# reDotSmart_0402_rev2.net
KiCad netlist of a schematic drawn in EAGLE
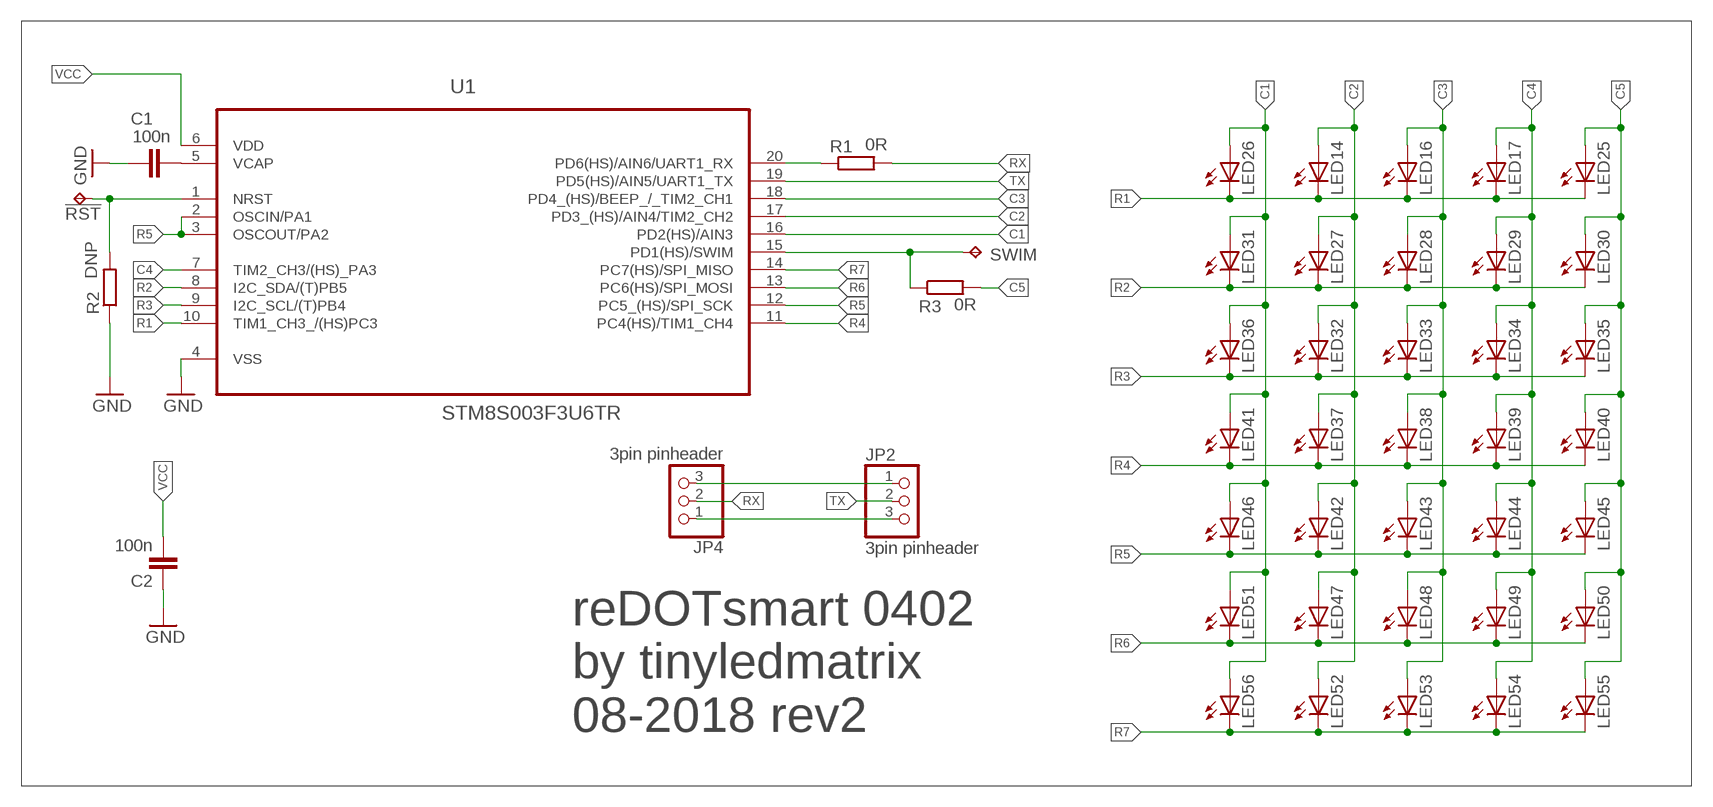
[diagram p0: schematic, sheet 1]

(export (version "E")
  (design (tool "Eeschema 10.0.6"))
  (components
    (comp (ref "!RST")
      (value "TPTP10R")
      (footprint "eagle-import:TP10R")
      (libsource (lib "eagle-import") (part "TPTP10R"))
    )
    (comp (ref "C1")
      (value "100n")
      (footprint "eagle-import:C0402-VISHAY")
      (libsource (lib "eagle-import") (part "C-EU0402_VISHAY"))
    )
    (comp (ref "C2")
      (value "100n")
      (footprint "eagle-import:C0402-VISHAY")
      (libsource (lib "eagle-import") (part "C-EU0402_VISHAY"))
    )
    (comp (ref "JP2")
      (value "3pin pinheader")
      (footprint "eagle-import:1X03_ROUND_NOSM")
      (libsource (lib "eagle-import") (part "PINHD-1X3NOSM"))
    )
    (comp (ref "JP4")
      (value "3pin pinheader")
      (footprint "eagle-import:1X03_ROUND_NOSM")
      (libsource (lib "eagle-import") (part "PINHD-1X3NOSM"))
    )
    (comp (ref "LED14")
      (value "LED0402_ROHM")
      (footprint "eagle-import:LED0402_E_ROHM_SML-P1")
      (libsource (lib "eagle-import") (part "LED0402_ROHM"))
    )
    (comp (ref "LED16")
      (value "LED0402_ROHM")
      (footprint "eagle-import:LED0402_E_ROHM_SML-P1")
      (libsource (lib "eagle-import") (part "LED0402_ROHM"))
    )
    (comp (ref "LED17")
      (value "LED0402_ROHM")
      (footprint "eagle-import:LED0402_E_ROHM_SML-P1")
      (libsource (lib "eagle-import") (part "LED0402_ROHM"))
    )
    (comp (ref "LED25")
      (value "LED0402_ROHM")
      (footprint "eagle-import:LED0402_E_ROHM_SML-P1")
      (libsource (lib "eagle-import") (part "LED0402_ROHM"))
    )
    (comp (ref "LED26")
      (value "LED0402_ROHM")
      (footprint "eagle-import:LED0402_E_ROHM_SML-P1")
      (libsource (lib "eagle-import") (part "LED0402_ROHM"))
    )
    (comp (ref "LED27")
      (value "LED0402_ROHM")
      (footprint "eagle-import:LED0402_E_ROHM_SML-P1")
      (libsource (lib "eagle-import") (part "LED0402_ROHM"))
    )
    (comp (ref "LED28")
      (value "LED0402_ROHM")
      (footprint "eagle-import:LED0402_E_ROHM_SML-P1")
      (libsource (lib "eagle-import") (part "LED0402_ROHM"))
    )
    (comp (ref "LED29")
      (value "LED0402_ROHM")
      (footprint "eagle-import:LED0402_E_ROHM_SML-P1")
      (libsource (lib "eagle-import") (part "LED0402_ROHM"))
    )
    (comp (ref "LED30")
      (value "LED0402_ROHM")
      (footprint "eagle-import:LED0402_E_ROHM_SML-P1")
      (libsource (lib "eagle-import") (part "LED0402_ROHM"))
    )
    (comp (ref "LED31")
      (value "LED0402_ROHM")
      (footprint "eagle-import:LED0402_E_ROHM_SML-P1")
      (libsource (lib "eagle-import") (part "LED0402_ROHM"))
    )
    (comp (ref "LED32")
      (value "LED0402_ROHM")
      (footprint "eagle-import:LED0402_E_ROHM_SML-P1")
      (libsource (lib "eagle-import") (part "LED0402_ROHM"))
    )
    (comp (ref "LED33")
      (value "LED0402_ROHM")
      (footprint "eagle-import:LED0402_E_ROHM_SML-P1")
      (libsource (lib "eagle-import") (part "LED0402_ROHM"))
    )
    (comp (ref "LED34")
      (value "LED0402_ROHM")
      (footprint "eagle-import:LED0402_E_ROHM_SML-P1")
      (libsource (lib "eagle-import") (part "LED0402_ROHM"))
    )
    (comp (ref "LED35")
      (value "LED0402_ROHM")
      (footprint "eagle-import:LED0402_E_ROHM_SML-P1")
      (libsource (lib "eagle-import") (part "LED0402_ROHM"))
    )
    (comp (ref "LED36")
      (value "LED0402_ROHM")
      (footprint "eagle-import:LED0402_E_ROHM_SML-P1")
      (libsource (lib "eagle-import") (part "LED0402_ROHM"))
    )
    (comp (ref "LED37")
      (value "LED0402_ROHM")
      (footprint "eagle-import:LED0402_E_ROHM_SML-P1")
      (libsource (lib "eagle-import") (part "LED0402_ROHM"))
    )
    (comp (ref "LED38")
      (value "LED0402_ROHM")
      (footprint "eagle-import:LED0402_E_ROHM_SML-P1")
      (libsource (lib "eagle-import") (part "LED0402_ROHM"))
    )
    (comp (ref "LED39")
      (value "LED0402_ROHM")
      (footprint "eagle-import:LED0402_E_ROHM_SML-P1")
      (libsource (lib "eagle-import") (part "LED0402_ROHM"))
    )
    (comp (ref "LED40")
      (value "LED0402_ROHM")
      (footprint "eagle-import:LED0402_E_ROHM_SML-P1")
      (libsource (lib "eagle-import") (part "LED0402_ROHM"))
    )
    (comp (ref "LED41")
      (value "LED0402_ROHM")
      (footprint "eagle-import:LED0402_E_ROHM_SML-P1")
      (libsource (lib "eagle-import") (part "LED0402_ROHM"))
    )
    (comp (ref "LED42")
      (value "LED0402_ROHM")
      (footprint "eagle-import:LED0402_E_ROHM_SML-P1")
      (libsource (lib "eagle-import") (part "LED0402_ROHM"))
    )
    (comp (ref "LED43")
      (value "LED0402_ROHM")
      (footprint "eagle-import:LED0402_E_ROHM_SML-P1")
      (libsource (lib "eagle-import") (part "LED0402_ROHM"))
    )
    (comp (ref "LED44")
      (value "LED0402_ROHM")
      (footprint "eagle-import:LED0402_E_ROHM_SML-P1")
      (libsource (lib "eagle-import") (part "LED0402_ROHM"))
    )
    (comp (ref "LED45")
      (value "LED0402_ROHM")
      (footprint "eagle-import:LED0402_E_ROHM_SML-P1")
      (libsource (lib "eagle-import") (part "LED0402_ROHM"))
    )
    (comp (ref "LED46")
      (value "LED0402_ROHM")
      (footprint "eagle-import:LED0402_E_ROHM_SML-P1")
      (libsource (lib "eagle-import") (part "LED0402_ROHM"))
    )
    (comp (ref "LED47")
      (value "LED0402_ROHM")
      (footprint "eagle-import:LED0402_E_ROHM_SML-P1")
      (libsource (lib "eagle-import") (part "LED0402_ROHM"))
    )
    (comp (ref "LED48")
      (value "LED0402_ROHM")
      (footprint "eagle-import:LED0402_E_ROHM_SML-P1")
      (libsource (lib "eagle-import") (part "LED0402_ROHM"))
    )
    (comp (ref "LED49")
      (value "LED0402_ROHM")
      (footprint "eagle-import:LED0402_E_ROHM_SML-P1")
      (libsource (lib "eagle-import") (part "LED0402_ROHM"))
    )
    (comp (ref "LED50")
      (value "LED0402_ROHM")
      (footprint "eagle-import:LED0402_E_ROHM_SML-P1")
      (libsource (lib "eagle-import") (part "LED0402_ROHM"))
    )
    (comp (ref "LED51")
      (value "LED0402_ROHM")
      (footprint "eagle-import:LED0402_E_ROHM_SML-P1")
      (libsource (lib "eagle-import") (part "LED0402_ROHM"))
    )
    (comp (ref "LED52")
      (value "LED0402_ROHM")
      (footprint "eagle-import:LED0402_E_ROHM_SML-P1")
      (libsource (lib "eagle-import") (part "LED0402_ROHM"))
    )
    (comp (ref "LED53")
      (value "LED0402_ROHM")
      (footprint "eagle-import:LED0402_E_ROHM_SML-P1")
      (libsource (lib "eagle-import") (part "LED0402_ROHM"))
    )
    (comp (ref "LED54")
      (value "LED0402_ROHM")
      (footprint "eagle-import:LED0402_E_ROHM_SML-P1")
      (libsource (lib "eagle-import") (part "LED0402_ROHM"))
    )
    (comp (ref "LED55")
      (value "LED0402_ROHM")
      (footprint "eagle-import:LED0402_E_ROHM_SML-P1")
      (libsource (lib "eagle-import") (part "LED0402_ROHM"))
    )
    (comp (ref "LED56")
      (value "LED0402_ROHM")
      (footprint "eagle-import:LED0402_E_ROHM_SML-P1")
      (libsource (lib "eagle-import") (part "LED0402_ROHM"))
    )
    (comp (ref "R1")
      (value "0R")
      (footprint "eagle-import:ADAFRUIT_R0402-VISHAY")
      (libsource (lib "eagle-import") (part "R-EU_R0402-VISHAY"))
    )
    (comp (ref "R2")
      (value "DNP")
      (footprint "eagle-import:ADAFRUIT_R0402-VISHAY")
      (libsource (lib "eagle-import") (part "R-EU_R0402-VISHAY"))
    )
    (comp (ref "R3")
      (value "0R")
      (footprint "eagle-import:ADAFRUIT_R0603-VISHAY")
      (libsource (lib "eagle-import") (part "R-EU_R0603-VISHAY"))
    )
    (comp (ref "SWIM")
      (value "TPTP10R")
      (footprint "eagle-import:TP10R")
      (libsource (lib "eagle-import") (part "TPTP10R"))
    )
    (comp (ref "U1")
      (value "STM8S003F3U6TR")
      (footprint "eagle-import:QFN50P300X300X100-20N_STM")
      (libsource (lib "eagle-import") (part "STM8S003F3U6TR"))
    )
  )
  (nets
    (net (code "1") (name "C1") (class "Default")
      (node (ref "LED26") (pin "A") (pinfunction "A_A") (pintype "passive"))
      (node (ref "LED31") (pin "A") (pinfunction "A_A") (pintype "passive"))
      (node (ref "LED36") (pin "A") (pinfunction "A_A") (pintype "passive"))
      (node (ref "LED41") (pin "A") (pinfunction "A_A") (pintype "passive"))
      (node (ref "LED46") (pin "A") (pinfunction "A_A") (pintype "passive"))
      (node (ref "LED51") (pin "A") (pinfunction "A_A") (pintype "passive"))
      (node (ref "LED56") (pin "A") (pinfunction "A_A") (pintype "passive"))
      (node (ref "U1") (pin "16") (pinfunction "PD2(HS)/AIN3_16") (pintype "bidirectional"))
    )
    (net (code "2") (name "C2") (class "Default")
      (node (ref "LED14") (pin "A") (pinfunction "A_A") (pintype "passive"))
      (node (ref "LED27") (pin "A") (pinfunction "A_A") (pintype "passive"))
      (node (ref "LED32") (pin "A") (pinfunction "A_A") (pintype "passive"))
      (node (ref "LED37") (pin "A") (pinfunction "A_A") (pintype "passive"))
      (node (ref "LED42") (pin "A") (pinfunction "A_A") (pintype "passive"))
      (node (ref "LED47") (pin "A") (pinfunction "A_A") (pintype "passive"))
      (node (ref "LED52") (pin "A") (pinfunction "A_A") (pintype "passive"))
      (node (ref "U1") (pin "17") (pinfunction "PD3_(HS)/AIN4/TIM2_CH2_17") (pintype "bidirectional"))
    )
    (net (code "3") (name "C3") (class "Default")
      (node (ref "LED16") (pin "A") (pinfunction "A_A") (pintype "passive"))
      (node (ref "LED28") (pin "A") (pinfunction "A_A") (pintype "passive"))
      (node (ref "LED33") (pin "A") (pinfunction "A_A") (pintype "passive"))
      (node (ref "LED38") (pin "A") (pinfunction "A_A") (pintype "passive"))
      (node (ref "LED43") (pin "A") (pinfunction "A_A") (pintype "passive"))
      (node (ref "LED48") (pin "A") (pinfunction "A_A") (pintype "passive"))
      (node (ref "LED53") (pin "A") (pinfunction "A_A") (pintype "passive"))
      (node (ref "U1") (pin "18") (pinfunction "PD4_(HS)/BEEP_/_TIM2_CH1_18") (pintype "bidirectional"))
    )
    (net (code "4") (name "C4") (class "Default")
      (node (ref "LED17") (pin "A") (pinfunction "A_A") (pintype "passive"))
      (node (ref "LED29") (pin "A") (pinfunction "A_A") (pintype "passive"))
      (node (ref "LED34") (pin "A") (pinfunction "A_A") (pintype "passive"))
      (node (ref "LED39") (pin "A") (pinfunction "A_A") (pintype "passive"))
      (node (ref "LED44") (pin "A") (pinfunction "A_A") (pintype "passive"))
      (node (ref "LED49") (pin "A") (pinfunction "A_A") (pintype "passive"))
      (node (ref "LED54") (pin "A") (pinfunction "A_A") (pintype "passive"))
      (node (ref "U1") (pin "7") (pinfunction "TIM2_CH3/(HS)_PA3_7") (pintype "bidirectional"))
    )
    (net (code "5") (name "C5") (class "Default")
      (node (ref "LED25") (pin "A") (pinfunction "A_A") (pintype "passive"))
      (node (ref "LED30") (pin "A") (pinfunction "A_A") (pintype "passive"))
      (node (ref "LED35") (pin "A") (pinfunction "A_A") (pintype "passive"))
      (node (ref "LED40") (pin "A") (pinfunction "A_A") (pintype "passive"))
      (node (ref "LED45") (pin "A") (pinfunction "A_A") (pintype "passive"))
      (node (ref "LED50") (pin "A") (pinfunction "A_A") (pintype "passive"))
      (node (ref "LED55") (pin "A") (pinfunction "A_A") (pintype "passive"))
      (node (ref "R3") (pin "2") (pinfunction "2_2") (pintype "passive"))
    )
    (net (code "6") (name "GND") (class "Default")
      (node (ref "C1") (pin "1") (pinfunction "1_1") (pintype "passive"))
      (node (ref "C2") (pin "1") (pinfunction "1_1") (pintype "passive"))
      (node (ref "JP2") (pin "1") (pinfunction "1_1") (pintype "passive"))
      (node (ref "JP4") (pin "3") (pinfunction "3_3") (pintype "passive"))
      (node (ref "R2") (pin "1") (pinfunction "1_1") (pintype "passive"))
      (node (ref "U1") (pin "4") (pinfunction "VSS_4") (pintype "power_in"))
    )
    (net (code "7") (name "Net-(U1-NRST)") (class "Default")
      (node (ref "!RST") (pin "TP") (pinfunction "TP_TP") (pintype "input"))
      (node (ref "R2") (pin "2") (pinfunction "2_2") (pintype "passive"))
      (node (ref "U1") (pin "1") (pinfunction "NRST_1") (pintype "bidirectional"))
    )
    (net (code "8") (name "Net-(U1-PD1(HS){slash}SWIM)") (class "Default")
      (node (ref "R3") (pin "1") (pinfunction "1_1") (pintype "passive"))
      (node (ref "SWIM") (pin "TP") (pinfunction "TP_TP") (pintype "input"))
      (node (ref "U1") (pin "15") (pinfunction "PD1(HS)/SWIM_15") (pintype "bidirectional"))
    )
    (net (code "9") (name "Net-(U1-PD6(HS){slash}AIN6{slash}UART1_RX)") (class "Default")
      (node (ref "R1") (pin "1") (pinfunction "1_1") (pintype "passive"))
      (node (ref "U1") (pin "20") (pinfunction "PD6(HS)/AIN6/UART1_RX_20") (pintype "bidirectional"))
    )
    (net (code "10") (name "Net-(U1-VCAP)") (class "Default")
      (node (ref "C1") (pin "2") (pinfunction "2_2") (pintype "passive"))
      (node (ref "U1") (pin "5") (pinfunction "VCAP_5") (pintype "power_in"))
    )
    (net (code "11") (name "R1") (class "Default")
      (node (ref "LED14") (pin "K") (pinfunction "C_K") (pintype "passive"))
      (node (ref "LED16") (pin "K") (pinfunction "C_K") (pintype "passive"))
      (node (ref "LED17") (pin "K") (pinfunction "C_K") (pintype "passive"))
      (node (ref "LED25") (pin "K") (pinfunction "C_K") (pintype "passive"))
      (node (ref "LED26") (pin "K") (pinfunction "C_K") (pintype "passive"))
      (node (ref "U1") (pin "10") (pinfunction "TIM1_CH3_/(HS)PC3_10") (pintype "bidirectional"))
    )
    (net (code "12") (name "R2") (class "Default")
      (node (ref "LED27") (pin "K") (pinfunction "C_K") (pintype "passive"))
      (node (ref "LED28") (pin "K") (pinfunction "C_K") (pintype "passive"))
      (node (ref "LED29") (pin "K") (pinfunction "C_K") (pintype "passive"))
      (node (ref "LED30") (pin "K") (pinfunction "C_K") (pintype "passive"))
      (node (ref "LED31") (pin "K") (pinfunction "C_K") (pintype "passive"))
      (node (ref "U1") (pin "8") (pinfunction "I2C_SDA/(T)PB5_8") (pintype "bidirectional"))
    )
    (net (code "13") (name "R3") (class "Default")
      (node (ref "LED32") (pin "K") (pinfunction "C_K") (pintype "passive"))
      (node (ref "LED33") (pin "K") (pinfunction "C_K") (pintype "passive"))
      (node (ref "LED34") (pin "K") (pinfunction "C_K") (pintype "passive"))
      (node (ref "LED35") (pin "K") (pinfunction "C_K") (pintype "passive"))
      (node (ref "LED36") (pin "K") (pinfunction "C_K") (pintype "passive"))
      (node (ref "U1") (pin "9") (pinfunction "I2C_SCL/(T)PB4_9") (pintype "bidirectional"))
    )
    (net (code "14") (name "R4") (class "Default")
      (node (ref "LED37") (pin "K") (pinfunction "C_K") (pintype "passive"))
      (node (ref "LED38") (pin "K") (pinfunction "C_K") (pintype "passive"))
      (node (ref "LED39") (pin "K") (pinfunction "C_K") (pintype "passive"))
      (node (ref "LED40") (pin "K") (pinfunction "C_K") (pintype "passive"))
      (node (ref "LED41") (pin "K") (pinfunction "C_K") (pintype "passive"))
      (node (ref "U1") (pin "11") (pinfunction "PC4(HS)/TIM1_CH4_11") (pintype "bidirectional"))
    )
    (net (code "15") (name "R5") (class "Default")
      (node (ref "LED42") (pin "K") (pinfunction "C_K") (pintype "passive"))
      (node (ref "LED43") (pin "K") (pinfunction "C_K") (pintype "passive"))
      (node (ref "LED44") (pin "K") (pinfunction "C_K") (pintype "passive"))
      (node (ref "LED45") (pin "K") (pinfunction "C_K") (pintype "passive"))
      (node (ref "LED46") (pin "K") (pinfunction "C_K") (pintype "passive"))
      (node (ref "U1") (pin "12") (pinfunction "PC5_(HS)/SPI_SCK_12") (pintype "bidirectional"))
      (node (ref "U1") (pin "2") (pinfunction "OSCIN/PA1_2") (pintype "bidirectional"))
      (node (ref "U1") (pin "3") (pinfunction "OSCOUT/PA2_3") (pintype "bidirectional"))
    )
    (net (code "16") (name "R6") (class "Default")
      (node (ref "LED47") (pin "K") (pinfunction "C_K") (pintype "passive"))
      (node (ref "LED48") (pin "K") (pinfunction "C_K") (pintype "passive"))
      (node (ref "LED49") (pin "K") (pinfunction "C_K") (pintype "passive"))
      (node (ref "LED50") (pin "K") (pinfunction "C_K") (pintype "passive"))
      (node (ref "LED51") (pin "K") (pinfunction "C_K") (pintype "passive"))
      (node (ref "U1") (pin "13") (pinfunction "PC6(HS)/SPI_MOSI_13") (pintype "bidirectional"))
    )
    (net (code "17") (name "R7") (class "Default")
      (node (ref "LED52") (pin "K") (pinfunction "C_K") (pintype "passive"))
      (node (ref "LED53") (pin "K") (pinfunction "C_K") (pintype "passive"))
      (node (ref "LED54") (pin "K") (pinfunction "C_K") (pintype "passive"))
      (node (ref "LED55") (pin "K") (pinfunction "C_K") (pintype "passive"))
      (node (ref "LED56") (pin "K") (pinfunction "C_K") (pintype "passive"))
      (node (ref "U1") (pin "14") (pinfunction "PC7(HS)/SPI_MISO_14") (pintype "bidirectional"))
    )
    (net (code "18") (name "RX") (class "Default")
      (node (ref "JP4") (pin "2") (pinfunction "2_2") (pintype "passive"))
      (node (ref "R1") (pin "2") (pinfunction "2_2") (pintype "passive"))
    )
    (net (code "19") (name "TX") (class "Default")
      (node (ref "JP2") (pin "2") (pinfunction "2_2") (pintype "passive"))
      (node (ref "U1") (pin "19") (pinfunction "PD5(HS)/AIN5/UART1_TX_19") (pintype "bidirectional"))
    )
    (net (code "20") (name "VCC") (class "Default")
      (node (ref "C2") (pin "2") (pinfunction "2_2") (pintype "passive"))
      (node (ref "JP2") (pin "3") (pinfunction "3_3") (pintype "passive"))
      (node (ref "JP4") (pin "1") (pinfunction "1_1") (pintype "passive"))
      (node (ref "U1") (pin "6") (pinfunction "VDD_6") (pintype "power_in"))
    )
  )
)
